# RS485.net
KiCad netlist of a schematic drawn in Altium Designer
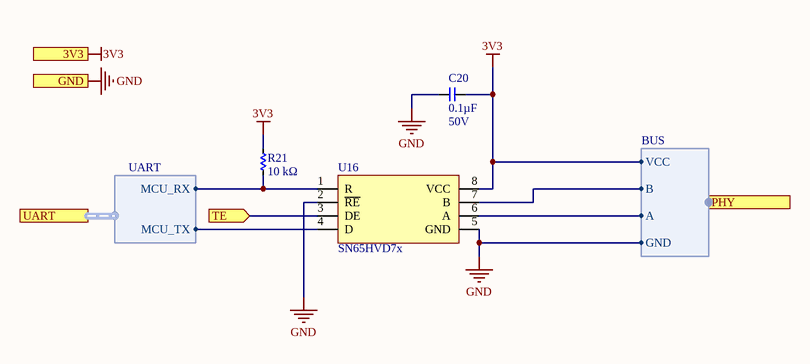
[diagram p0: RS485.SchDoc]

(export (version "E")
  (design (tool "Eeschema 10.0.6"))
  (components
    (comp (ref "C20")
      (value "490-1519-1-ND")
      (footprint "C0603")
      (description "CAP CER 0603 0.1µF X7R 50V 10%")
      (fields
        (field (name "CAPACITANCE (SHORTHAND)") "0.1µF")
        (field (name "MANUFACTURER") "Murata Electronics North America")
        (field (name "RATED VOLTAGE") "50V")
      )
      (libsource (lib "Stanford Student Space Initiative") (part "__template_cap"))
    )
    (comp (ref "R21")
      (value "311-10.0KHRCT-ND")
      (footprint "R0603")
      (description "RES SMD 10K OHM 1% 1/10W 0603")
      (fields
        (field (name "MANUFACTURER PART NUMBER") "RC0603FR-0710KL")
        (field (name "MANUFACTURER") "Yageo")
        (field (name "RESISTANCE") "10 kΩ")
      )
      (libsource (lib "Stanford Student Space Initiative") (part "__template_resistor"))
    )
    (comp (ref "U16")
      (value "SN65HVD7x")
      (footprint "8SOIC150")
      (fields
        (field (name "MANUFACTURER") "Texas Instruments")
        (field (name "MANUFACTURER PART NUMBER") "SN65HVD72DGKR")
      )
      (libsource (lib "Stanford Student Space Initiative") (part "SN65HVD7x"))
    )
  )
  (nets
    (net (code "3") (name "/A") (class "Default")
      (node (ref "U16") (pin "6") (pinfunction "A_6") (pintype "passive"))
    )
    (net (code "4") (name "/B") (class "Default")
      (node (ref "U16") (pin "7") (pinfunction "B_7") (pintype "passive"))
    )
    (net (code "5") (name "/MCU_RX") (class "Default")
      (node (ref "R21") (pin "2") (pintype "passive"))
      (node (ref "U16") (pin "1") (pinfunction "R_1") (pintype "passive"))
    )
    (net (code "6") (name "/MCU_TX") (class "Default")
      (node (ref "U16") (pin "4") (pinfunction "D_4") (pintype "passive"))
    )
    (net (code "7") (name "/TE") (class "Default")
      (node (ref "U16") (pin "3") (pinfunction "DE_3") (pintype "passive"))
    )
    (net (code "10") (name "3V3") (class "Default")
      (node (ref "C20") (pin "2") (pintype "passive"))
      (node (ref "R21") (pin "1") (pintype "passive"))
      (node (ref "U16") (pin "8") (pinfunction "VCC_8") (pintype "passive"))
    )
    (net (code "11") (name "GND") (class "Default")
      (node (ref "C20") (pin "1") (pintype "passive"))
      (node (ref "U16") (pin "2") (pinfunction "~{RE}_2") (pintype "passive"))
      (node (ref "U16") (pin "5") (pinfunction "GND_5") (pintype "passive"))
    )
  )
)
